# ESP8266_Amp_SMD.net
KiCad netlist of a schematic drawn in Altium Designer
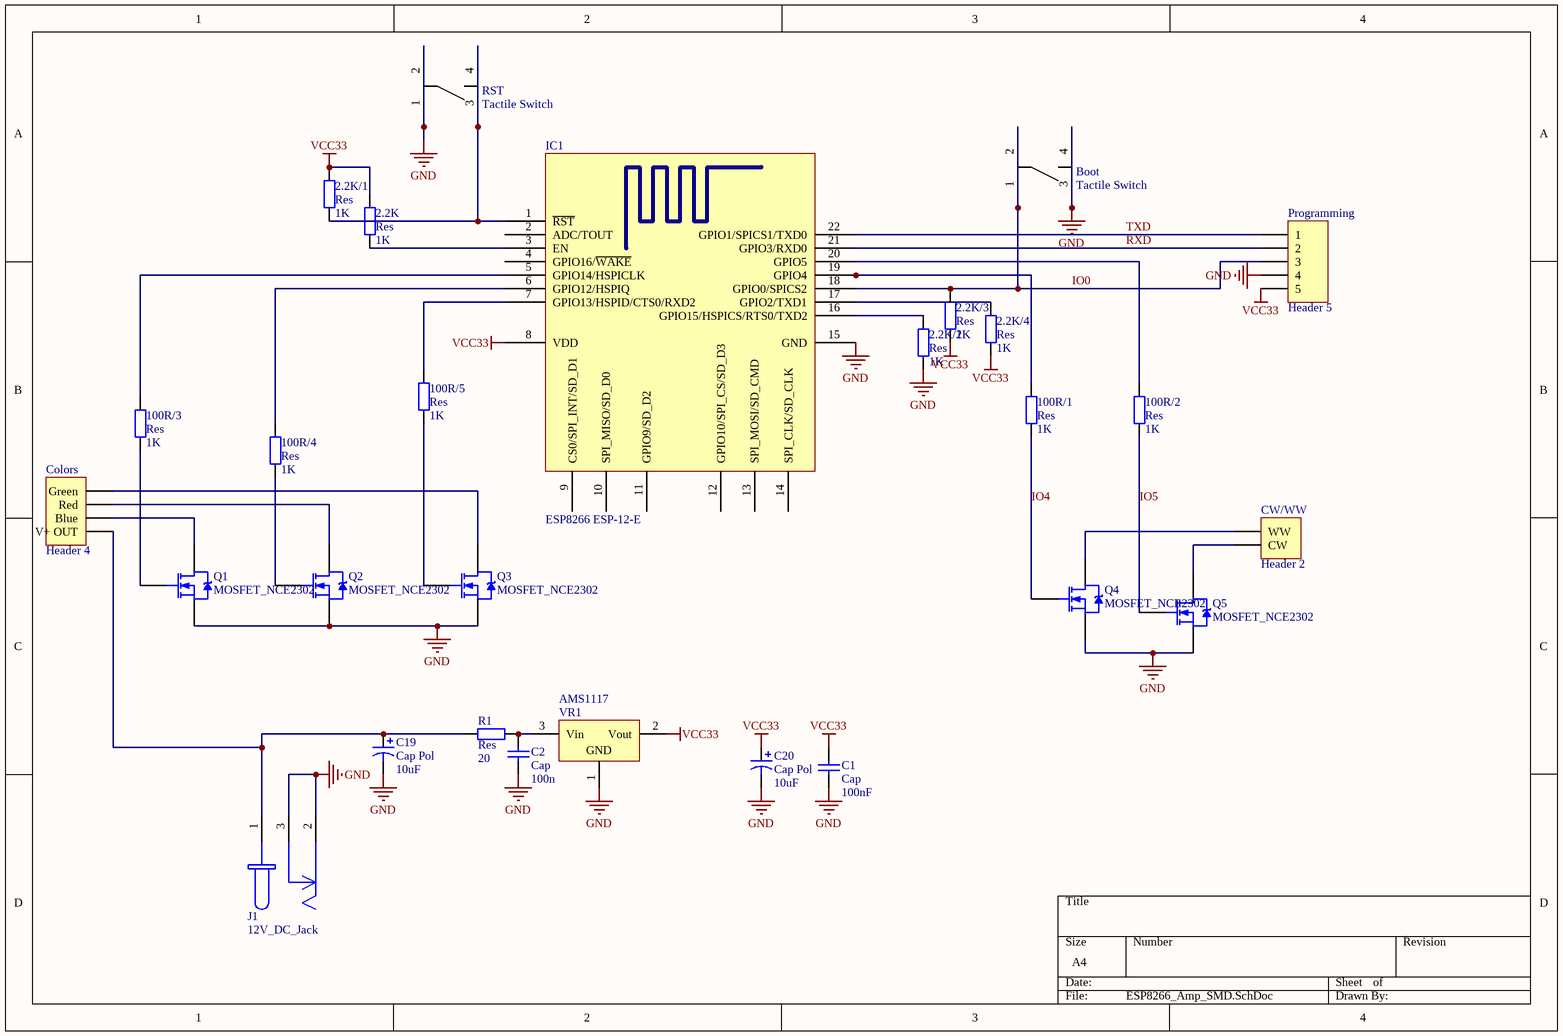
[diagram p0: ESP8266_Amp_SMD.SchDoc]

(export (version "E")
  (design (tool "Eeschema 10.0.6"))
  (components
    (comp (ref "2.2K")
      (value "Res")
      (footprint "0805")
      (description "Resistor")
      (fields (field (name "ALTIUM_VALUE") "1K") (field (name "PUBLISHER") "Altium Limited"))
      (libsource (lib "cadLib") (part "Res"))
    )
    (comp (ref "2.2K/1")
      (value "Res")
      (footprint "0805")
      (description "Resistor")
      (fields (field (name "ALTIUM_VALUE") "1K") (field (name "PUBLISHER") "Altium Limited"))
      (libsource (lib "cadLib") (part "Res"))
    )
    (comp (ref "2.2K/2")
      (value "Res")
      (footprint "0805")
      (description "Resistor")
      (fields (field (name "ALTIUM_VALUE") "1K") (field (name "PUBLISHER") "Altium Limited"))
      (libsource (lib "cadLib") (part "Res"))
    )
    (comp (ref "2.2K/3")
      (value "Res")
      (footprint "0805")
      (description "Resistor")
      (fields (field (name "ALTIUM_VALUE") "1K") (field (name "PUBLISHER") "Altium Limited"))
      (libsource (lib "cadLib") (part "Res"))
    )
    (comp (ref "2.2K/4")
      (value "Res")
      (footprint "0805")
      (description "Resistor")
      (fields (field (name "ALTIUM_VALUE") "1K") (field (name "PUBLISHER") "Altium Limited"))
      (libsource (lib "cadLib") (part "Res"))
    )
    (comp (ref "100R/1")
      (value "Res")
      (footprint "0805")
      (description "Resistor")
      (fields (field (name "ALTIUM_VALUE") "1K") (field (name "PUBLISHER") "Altium Limited"))
      (libsource (lib "cadLib") (part "Res"))
    )
    (comp (ref "100R/2")
      (value "Res")
      (footprint "0805")
      (description "Resistor")
      (fields (field (name "ALTIUM_VALUE") "1K") (field (name "PUBLISHER") "Altium Limited"))
      (libsource (lib "cadLib") (part "Res"))
    )
    (comp (ref "100R/3")
      (value "Res")
      (footprint "0805")
      (description "Resistor")
      (fields (field (name "ALTIUM_VALUE") "1K") (field (name "PUBLISHER") "Altium Limited"))
      (libsource (lib "cadLib") (part "Res"))
    )
    (comp (ref "100R/4")
      (value "Res")
      (footprint "0805")
      (description "Resistor")
      (fields (field (name "ALTIUM_VALUE") "1K") (field (name "PUBLISHER") "Altium Limited"))
      (libsource (lib "cadLib") (part "Res"))
    )
    (comp (ref "100R/5")
      (value "Res")
      (footprint "0805")
      (description "Resistor")
      (fields (field (name "ALTIUM_VALUE") "1K") (field (name "PUBLISHER") "Altium Limited"))
      (libsource (lib "cadLib") (part "Res"))
    )
    (comp (ref "Boot")
      (value "Tactile Switch")
      (footprint "Tactile-SW SMT")
      (fields (field (name "PUBLISHER") "Altium Limited"))
      (libsource (lib "cadLib") (part "Tact_SW"))
    )
    (comp (ref "C1")
      (value "Cap")
      (footprint "0805")
      (description "Capacitor")
      (fields (field (name "ALTIUM_VALUE") "100nF") (field (name "PUBLISHER") "Altium Limited"))
      (libsource (lib "cadLib") (part "Cap"))
    )
    (comp (ref "C2")
      (value "Cap")
      (footprint "0805")
      (description "Capacitor")
      (fields (field (name "ALTIUM_VALUE") "100n") (field (name "PUBLISHER") "Altium Limited"))
      (libsource (lib "cadLib") (part "Cap"))
    )
    (comp (ref "C19")
      (value "Cap Pol")
      (footprint "CAPR-2.54mm")
      (description "Polarized Capacitor (Axial)")
      (fields (field (name "ALTIUM_VALUE") "10uF") (field (name "PUBLISHER") "Altium Limited"))
      (libsource (lib "cadLib") (part "Cap Pol"))
    )
    (comp (ref "C20")
      (value "Cap Pol")
      (footprint "CAPR-2.54mm")
      (description "Polarized Capacitor (Axial)")
      (fields (field (name "ALTIUM_VALUE") "10uF") (field (name "PUBLISHER") "Altium Limited"))
      (libsource (lib "cadLib") (part "Cap Pol"))
    )
    (comp (ref "Colors")
      (value "Header 4")
      (footprint "HDR1X4")
      (description "Header, 4-Pin")
      (fields (field (name "PUBLISHER") "Altium Limited"))
      (libsource (lib "Miscellaneous Connectors") (part "Header 4"))
    )
    (comp (ref "CW/WW")
      (value "Header 2")
      (footprint "HDR1X2")
      (description "Header, 2-Pin")
      (fields (field (name "PUBLISHER") "Altium Limited"))
      (libsource (lib "Miscellaneous Connectors") (part "Header 2"))
    )
    (comp (ref "IC1")
      (value "ESP8266 ESP-12-E")
      (footprint "ESP8266 ESP-12-E")
      (libsource (lib "cadLib") (part "ESP8266 ESP-12-E"))
    )
    (comp (ref "J1")
      (value "12V_DC_Jack")
      (footprint "694106301002")
      (description "WR-DC DC Power Jack Right Angled(6.4)")
      (fields (field (name "PARTNUMBER") "694106301002") (field (name "PUBLISHER") "Wurth Elektronik"))
      (libsource (lib "cadLib") (part "12V_DC_Jack"))
    )
    (comp (ref "Programming")
      (value "Header 5")
      (footprint "HDR1X5")
      (description "Header, 5-Pin")
      (fields (field (name "PUBLISHER") "Altium Limited"))
      (libsource (lib "Miscellaneous Connectors") (part "Header 5"))
    )
    (comp (ref "Q1")
      (value "MOSFET_NCE2302")
      (footprint "SOT23")
      (description "SOT-23 MOSFET, Vgs_th = 0.85V, Id_max = 4A, Vds_max = 20V")
      (fields (field (name "PUBLISHER") "Altium Limited"))
      (libsource (lib "cadLib") (part "MOSFET_NCE2302"))
    )
    (comp (ref "Q2")
      (value "MOSFET_NCE2302")
      (footprint "SOT23")
      (description "SOT-23 MOSFET, Vgs_th = 0.85V, Id_max = 4A, Vds_max = 20V")
      (fields (field (name "PUBLISHER") "Altium Limited"))
      (libsource (lib "cadLib") (part "MOSFET_NCE2302"))
    )
    (comp (ref "Q3")
      (value "MOSFET_NCE2302")
      (footprint "SOT23")
      (description "SOT-23 MOSFET, Vgs_th = 0.85V, Id_max = 4A, Vds_max = 20V")
      (fields (field (name "PUBLISHER") "Altium Limited"))
      (libsource (lib "cadLib") (part "MOSFET_NCE2302"))
    )
    (comp (ref "Q4")
      (value "MOSFET_NCE2302")
      (footprint "SOT23")
      (description "SOT-23 MOSFET, Vgs_th = 0.85V, Id_max = 4A, Vds_max = 20V")
      (fields (field (name "PUBLISHER") "Altium Limited"))
      (libsource (lib "cadLib") (part "MOSFET_NCE2302"))
    )
    (comp (ref "Q5")
      (value "MOSFET_NCE2302")
      (footprint "SOT23")
      (description "SOT-23 MOSFET, Vgs_th = 0.85V, Id_max = 4A, Vds_max = 20V")
      (fields (field (name "PUBLISHER") "Altium Limited"))
      (libsource (lib "cadLib") (part "MOSFET_NCE2302"))
    )
    (comp (ref "R1")
      (value "Res")
      (footprint "0805")
      (description "Resistor")
      (fields (field (name "ALTIUM_VALUE") "20") (field (name "PUBLISHER") "Altium Limited"))
      (libsource (lib "") (part "Res_1"))
    )
    (comp (ref "RST")
      (value "Tactile Switch")
      (footprint "Tactile-SW SMT")
      (fields (field (name "PUBLISHER") "Altium Limited"))
      (libsource (lib "cadLib") (part "Tact_SW"))
    )
    (comp (ref "VR1")
      (value "AMS1117")
      (footprint "SOT89")
      (description "Voltage Regulator")
      (fields (field (name "PUBLISHER") "Altium Limited"))
      (libsource (lib "cadLib") (part "VoltageRegulator_G/O/I"))
    )
  )
  (nets
    (net (code "1") (name "/IO0") (class "Default")
      (node (ref "2.2K/3") (pin "2") (pinfunction "2_2") (pintype "passive"))
      (node (ref "Boot") (pin "1") (pinfunction "1_1") (pintype "passive"))
      (node (ref "Boot") (pin "2") (pinfunction "2_2") (pintype "passive"))
      (node (ref "IC1") (pin "18") (pinfunction "GPIO0/SPICS2_18") (pintype "passive"))
      (node (ref "Programming") (pin "3") (pinfunction "3_3") (pintype "passive"))
    )
    (net (code "2") (name "/IO4") (class "Default")
      (node (ref "100R/1") (pin "1") (pinfunction "1_1") (pintype "passive"))
      (node (ref "Q4") (pin "2") (pinfunction "G_2") (pintype "passive"))
    )
    (net (code "3") (name "/IO5") (class "Default")
      (node (ref "100R/2") (pin "1") (pinfunction "1_1") (pintype "passive"))
      (node (ref "Q5") (pin "2") (pinfunction "G_2") (pintype "passive"))
    )
    (net (code "4") (name "/RXD") (class "Default")
      (node (ref "IC1") (pin "21") (pinfunction "GPIO3/RXD0_21") (pintype "passive"))
      (node (ref "Programming") (pin "2") (pinfunction "2_2") (pintype "passive"))
    )
    (net (code "5") (name "/TXD") (class "Default")
      (node (ref "IC1") (pin "22") (pinfunction "GPIO1/SPICS1/TXD0_22") (pintype "passive"))
      (node (ref "Programming") (pin "1") (pinfunction "1_1") (pintype "passive"))
    )
    (net (code "6") (name "GND") (class "Default")
      (node (ref "2.2K/2") (pin "1") (pinfunction "1_1") (pintype "passive"))
      (node (ref "Boot") (pin "3") (pinfunction "3_3") (pintype "passive"))
      (node (ref "Boot") (pin "4") (pinfunction "4_4") (pintype "passive"))
      (node (ref "C1") (pin "1") (pinfunction "1_1") (pintype "passive"))
      (node (ref "C19") (pin "1") (pinfunction "1_1") (pintype "passive"))
      (node (ref "C2") (pin "1") (pinfunction "1_1") (pintype "passive"))
      (node (ref "C20") (pin "1") (pinfunction "1_1") (pintype "passive"))
      (node (ref "IC1") (pin "15") (pinfunction "GND_15") (pintype "passive"))
      (node (ref "J1") (pin "2") (pinfunction "2_2") (pintype "passive"))
      (node (ref "J1") (pin "3") (pinfunction "3_3") (pintype "passive"))
      (node (ref "Programming") (pin "4") (pinfunction "4_4") (pintype "passive"))
      (node (ref "Q1") (pin "1") (pinfunction "S_1") (pintype "passive"))
      (node (ref "Q2") (pin "1") (pinfunction "S_1") (pintype "passive"))
      (node (ref "Q3") (pin "1") (pinfunction "S_1") (pintype "passive"))
      (node (ref "Q4") (pin "1") (pinfunction "S_1") (pintype "passive"))
      (node (ref "Q5") (pin "1") (pinfunction "S_1") (pintype "passive"))
      (node (ref "RST") (pin "1") (pinfunction "1_1") (pintype "passive"))
      (node (ref "RST") (pin "2") (pinfunction "2_2") (pintype "passive"))
      (node (ref "VR1") (pin "1") (pinfunction "GND_1") (pintype "passive"))
    )
    (net (code "7") (name "Net-(CW/WW-CW)") (class "Default")
      (node (ref "CW/WW") (pin "2") (pinfunction "CW_2") (pintype "passive"))
      (node (ref "Q5") (pin "3") (pinfunction "D_3") (pintype "passive"))
    )
    (net (code "8") (name "Net-(CW/WW-WW)") (class "Default")
      (node (ref "CW/WW") (pin "1") (pinfunction "WW_1") (pintype "passive"))
      (node (ref "Q4") (pin "3") (pinfunction "D_3") (pintype "passive"))
    )
    (net (code "9") (name "Net-(Colors-Blue)") (class "Default")
      (node (ref "Colors") (pin "2") (pinfunction "Blue_2") (pintype "passive"))
      (node (ref "Q1") (pin "3") (pinfunction "D_3") (pintype "passive"))
    )
    (net (code "10") (name "Net-(Colors-Green)") (class "Default")
      (node (ref "Colors") (pin "4") (pinfunction "Green_4") (pintype "passive"))
      (node (ref "Q3") (pin "3") (pinfunction "D_3") (pintype "passive"))
    )
    (net (code "11") (name "Net-(Colors-Red)") (class "Default")
      (node (ref "Colors") (pin "3") (pinfunction "Red_3") (pintype "passive"))
      (node (ref "Q2") (pin "3") (pinfunction "D_3") (pintype "passive"))
    )
    (net (code "12") (name "Net-(Colors-V+_OUT)") (class "Default")
      (node (ref "C19") (pin "2") (pinfunction "2_2") (pintype "passive"))
      (node (ref "Colors") (pin "1") (pinfunction "V+_OUT_1") (pintype "passive"))
      (node (ref "J1") (pin "1") (pinfunction "1_1") (pintype "passive"))
      (node (ref "R1") (pin "1") (pinfunction "1_1") (pintype "passive"))
    )
    (net (code "13") (name "Net-(IC1-EN)") (class "Default")
      (node (ref "2.2K") (pin "1") (pinfunction "1_1") (pintype "passive"))
      (node (ref "IC1") (pin "3") (pinfunction "EN_3") (pintype "passive"))
    )
    (net (code "14") (name "Net-(IC1-GPIO2{slash}TXD1)") (class "Default")
      (node (ref "2.2K/4") (pin "2") (pinfunction "2_2") (pintype "passive"))
      (node (ref "IC1") (pin "17") (pinfunction "GPIO2/TXD1_17") (pintype "passive"))
    )
    (net (code "15") (name "Net-(IC1-GPIO4)") (class "Default")
      (node (ref "100R/1") (pin "2") (pinfunction "2_2") (pintype "passive"))
      (node (ref "IC1") (pin "19") (pinfunction "GPIO4_19") (pintype "passive"))
    )
    (net (code "16") (name "Net-(IC1-GPIO5)") (class "Default")
      (node (ref "100R/2") (pin "2") (pinfunction "2_2") (pintype "passive"))
      (node (ref "IC1") (pin "20") (pinfunction "GPIO5_20") (pintype "passive"))
    )
    (net (code "17") (name "Net-(IC1-GPIO12{slash}HSPIQ)") (class "Default")
      (node (ref "100R/4") (pin "2") (pinfunction "2_2") (pintype "passive"))
      (node (ref "IC1") (pin "6") (pinfunction "GPIO12/HSPIQ_6") (pintype "passive"))
    )
    (net (code "18") (name "Net-(IC1-GPIO13{slash}HSPID{slash}CTS0{slash}RXD2)") (class "Default")
      (node (ref "100R/5") (pin "2") (pinfunction "2_2") (pintype "passive"))
      (node (ref "IC1") (pin "7") (pinfunction "GPIO13/HSPID/CTS0/RXD2_7") (pintype "passive"))
    )
    (net (code "19") (name "Net-(IC1-GPIO14{slash}HSPICLK)") (class "Default")
      (node (ref "100R/3") (pin "2") (pinfunction "2_2") (pintype "passive"))
      (node (ref "IC1") (pin "5") (pinfunction "GPIO14/HSPICLK_5") (pintype "passive"))
    )
    (net (code "20") (name "Net-(IC1-GPIO15{slash}HSPICS{slash}RTS0{slash}TXD2)") (class "Default")
      (node (ref "2.2K/2") (pin "2") (pinfunction "2_2") (pintype "passive"))
      (node (ref "IC1") (pin "16") (pinfunction "GPIO15/HSPICS/RTS0/TXD2_16") (pintype "passive"))
    )
    (net (code "21") (name "Net-(IC1-~{RST})") (class "Default")
      (node (ref "2.2K/1") (pin "1") (pinfunction "1_1") (pintype "passive"))
      (node (ref "IC1") (pin "1") (pinfunction "~{RST}_1") (pintype "passive"))
      (node (ref "RST") (pin "3") (pinfunction "3_3") (pintype "passive"))
      (node (ref "RST") (pin "4") (pinfunction "4_4") (pintype "passive"))
    )
    (net (code "22") (name "Net-(Q1-G)") (class "Default")
      (node (ref "100R/3") (pin "1") (pinfunction "1_1") (pintype "passive"))
      (node (ref "Q1") (pin "2") (pinfunction "G_2") (pintype "passive"))
    )
    (net (code "23") (name "Net-(Q2-G)") (class "Default")
      (node (ref "100R/4") (pin "1") (pinfunction "1_1") (pintype "passive"))
      (node (ref "Q2") (pin "2") (pinfunction "G_2") (pintype "passive"))
    )
    (net (code "24") (name "Net-(Q3-G)") (class "Default")
      (node (ref "100R/5") (pin "1") (pinfunction "1_1") (pintype "passive"))
      (node (ref "Q3") (pin "2") (pinfunction "G_2") (pintype "passive"))
    )
    (net (code "25") (name "Net-(VR1-Vin)") (class "Default")
      (node (ref "C2") (pin "2") (pinfunction "2_2") (pintype "passive"))
      (node (ref "R1") (pin "2") (pinfunction "2_2") (pintype "passive"))
      (node (ref "VR1") (pin "3") (pinfunction "Vin_3") (pintype "passive"))
    )
    (net (code "26") (name "VCC33") (class "Default")
      (node (ref "2.2K") (pin "2") (pinfunction "2_2") (pintype "passive"))
      (node (ref "2.2K/1") (pin "2") (pinfunction "2_2") (pintype "passive"))
      (node (ref "2.2K/3") (pin "1") (pinfunction "1_1") (pintype "passive"))
      (node (ref "2.2K/4") (pin "1") (pinfunction "1_1") (pintype "passive"))
      (node (ref "C1") (pin "2") (pinfunction "2_2") (pintype "passive"))
      (node (ref "C20") (pin "2") (pinfunction "2_2") (pintype "passive"))
      (node (ref "IC1") (pin "8") (pinfunction "VDD_8") (pintype "passive"))
      (node (ref "Programming") (pin "5") (pinfunction "5_5") (pintype "passive"))
      (node (ref "VR1") (pin "2") (pinfunction "Vout_2") (pintype "passive"))
    )
    (net (code "27") (name "unconnected-(IC1-ADC{slash}TOUT-Pad2)") (class "Default")
      (node (ref "IC1") (pin "2") (pinfunction "ADC/TOUT_2") (pintype "passive"))
    )
    (net (code "28") (name "unconnected-(IC1-CS0{slash}SPI_INT{slash}SD_D1-Pad9)") (class "Default")
      (node (ref "IC1") (pin "9") (pinfunction "CS0/SPI_INT/SD_D1_9") (pintype "passive"))
    )
    (net (code "29") (name "unconnected-(IC1-GPIO9{slash}SD_D2-Pad11)") (class "Default")
      (node (ref "IC1") (pin "11") (pinfunction "GPIO9/SD_D2_11") (pintype "passive"))
    )
    (net (code "30") (name "unconnected-(IC1-GPIO10{slash}SPI_CS{slash}SD_D3-Pad12)") (class "Default")
      (node (ref "IC1") (pin "12") (pinfunction "GPIO10/SPI_CS/SD_D3_12") (pintype "passive"))
    )
    (net (code "31") (name "unconnected-(IC1-GPIO16{slash}~{WAKE}-Pad4)") (class "Default")
      (node (ref "IC1") (pin "4") (pinfunction "GPIO16/~{WAKE}_4") (pintype "passive"))
    )
    (net (code "32") (name "unconnected-(IC1-SPI_CLK{slash}SD_CLK-Pad14)") (class "Default")
      (node (ref "IC1") (pin "14") (pinfunction "SPI_CLK/SD_CLK_14") (pintype "passive"))
    )
    (net (code "33") (name "unconnected-(IC1-SPI_MISO{slash}SD_D0-Pad10)") (class "Default")
      (node (ref "IC1") (pin "10") (pinfunction "SPI_MISO/SD_D0_10") (pintype "passive"))
    )
    (net (code "34") (name "unconnected-(IC1-SPI_MOSI{slash}SD_CMD-Pad13)") (class "Default")
      (node (ref "IC1") (pin "13") (pinfunction "SPI_MOSI/SD_CMD_13") (pintype "passive"))
    )
  )
)
